# uC.net
KiCad netlist of a schematic drawn in Altium Designer
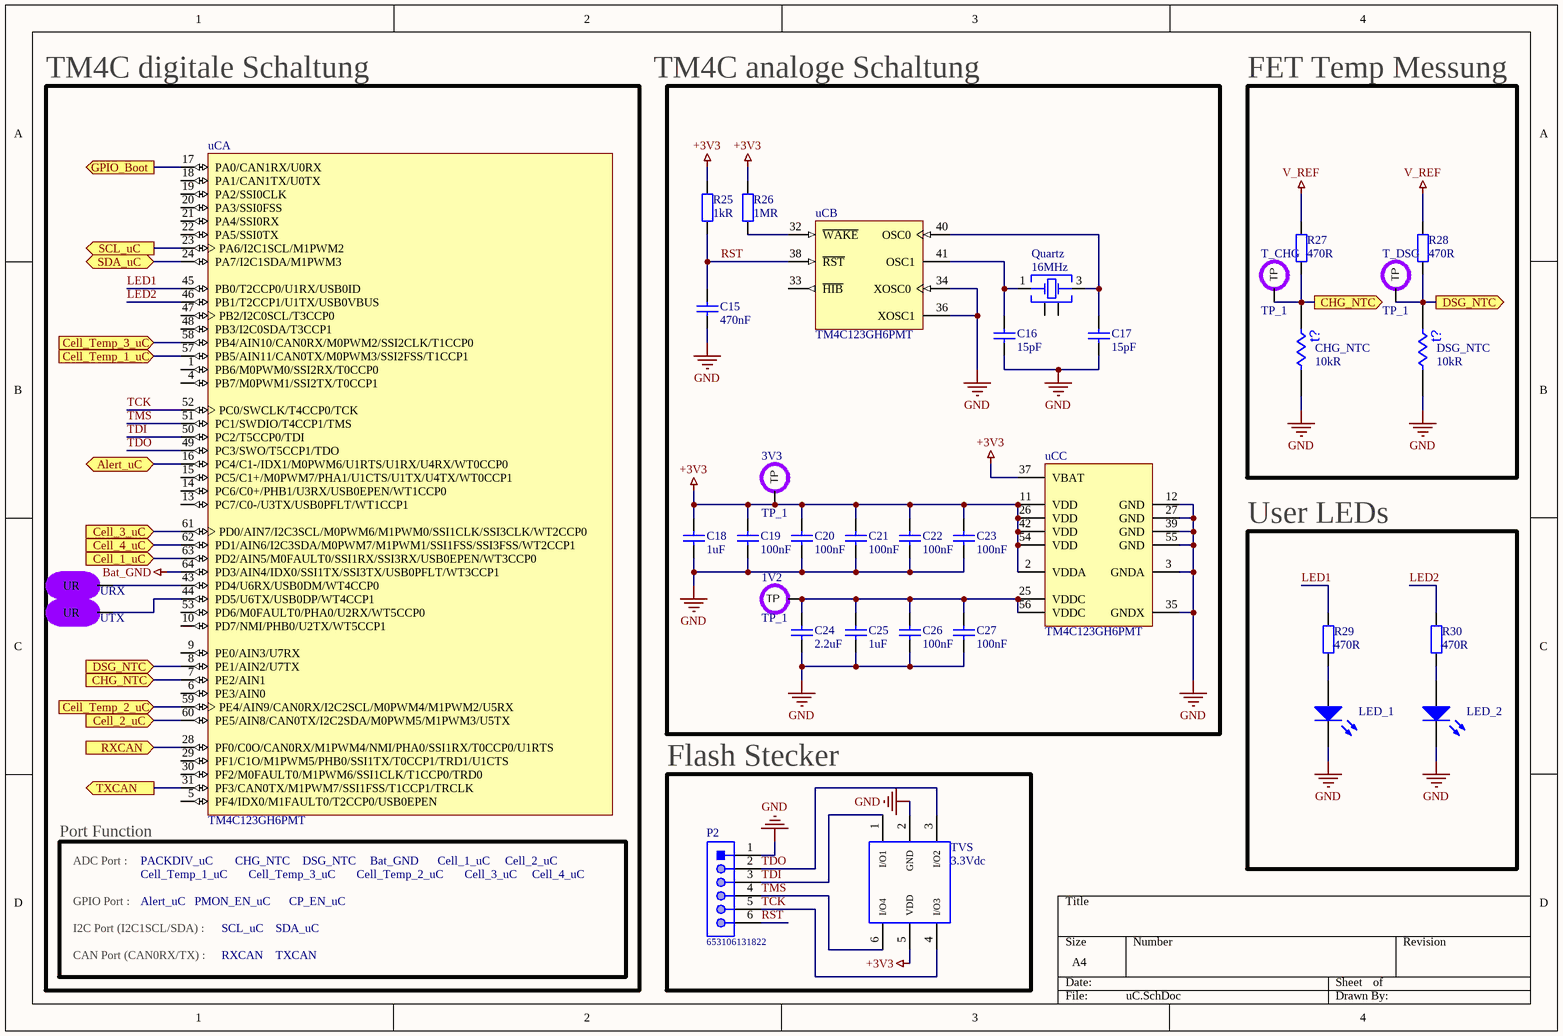
[diagram p0: uC.SchDoc]

(export (version "E")
  (design (tool "Eeschema 10.0.6"))
  (components
    (comp (ref "1V2")
      (value "TP_1")
      (footprint "Test point")
      (description "Power Supply for logical circuit")
      (libsource (lib "Schlib1") (part "Test point"))
    )
    (comp (ref "3V3")
      (value "TP_1")
      (footprint "Test point")
      (description "Power Supply for uC")
      (libsource (lib "Schlib1") (part "Test point"))
    )
    (comp (ref "C15")
      (value "470nF")
      (footprint "1608[0603]")
      (description "Capacitor")
      (fields (field (name "PUBLISHER") "Altium Limited"))
      (libsource (lib "Miscellaneous Devices") (part "Cap"))
    )
    (comp (ref "C16")
      (value "15pF")
      (footprint "1608[0603]")
      (description "Capacitor")
      (fields (field (name "PUBLISHER") "Altium Limited"))
      (libsource (lib "Miscellaneous Devices") (part "Cap"))
    )
    (comp (ref "C17")
      (value "15pF")
      (footprint "1608[0603]")
      (description "Capacitor")
      (fields (field (name "PUBLISHER") "Altium Limited"))
      (libsource (lib "Miscellaneous Devices") (part "Cap"))
    )
    (comp (ref "C18")
      (value "1uF")
      (footprint "1608[0603]")
      (description "Capacitor")
      (fields (field (name "PUBLISHER") "Altium Limited"))
      (libsource (lib "Miscellaneous Devices") (part "Cap"))
    )
    (comp (ref "C19")
      (value "100nF")
      (footprint "1608[0603]")
      (description "Capacitor")
      (fields (field (name "PUBLISHER") "Altium Limited"))
      (libsource (lib "Miscellaneous Devices") (part "Cap"))
    )
    (comp (ref "C20")
      (value "100nF")
      (footprint "1608[0603]")
      (description "Capacitor")
      (fields (field (name "PUBLISHER") "Altium Limited"))
      (libsource (lib "Miscellaneous Devices") (part "Cap"))
    )
    (comp (ref "C21")
      (value "100nF")
      (footprint "1608[0603]")
      (description "Capacitor")
      (fields (field (name "PUBLISHER") "Altium Limited"))
      (libsource (lib "Miscellaneous Devices") (part "Cap"))
    )
    (comp (ref "C22")
      (value "100nF")
      (footprint "1608[0603]")
      (description "Capacitor")
      (fields (field (name "PUBLISHER") "Altium Limited"))
      (libsource (lib "Miscellaneous Devices") (part "Cap"))
    )
    (comp (ref "C23")
      (value "100nF")
      (footprint "1608[0603]")
      (description "Capacitor")
      (fields (field (name "PUBLISHER") "Altium Limited"))
      (libsource (lib "Miscellaneous Devices") (part "Cap"))
    )
    (comp (ref "C24")
      (value "2.2uF")
      (footprint "1608[0603]")
      (description "Capacitor")
      (fields (field (name "PUBLISHER") "Altium Limited"))
      (libsource (lib "Miscellaneous Devices") (part "Cap"))
    )
    (comp (ref "C25")
      (value "1uF")
      (footprint "1608[0603]")
      (description "Capacitor")
      (fields (field (name "PUBLISHER") "Altium Limited"))
      (libsource (lib "Miscellaneous Devices") (part "Cap"))
    )
    (comp (ref "C26")
      (value "100nF")
      (footprint "1608[0603]")
      (description "Capacitor")
      (fields (field (name "PUBLISHER") "Altium Limited"))
      (libsource (lib "Miscellaneous Devices") (part "Cap"))
    )
    (comp (ref "C27")
      (value "100nF")
      (footprint "1608[0603]")
      (description "Capacitor")
      (fields (field (name "PUBLISHER") "Altium Limited"))
      (libsource (lib "Miscellaneous Devices") (part "Cap"))
    )
    (comp (ref "CHG_NTC")
      (value "10kR")
      (footprint "J1-0603")
      (description "Thermistor")
      (fields (field (name "PUBLISHER") "Altium Limited"))
      (libsource (lib "Miscellaneous Devices") (part "Res Thermal"))
    )
    (comp (ref "DSG_NTC")
      (value "10kR")
      (footprint "J1-0603")
      (description "Thermistor")
      (fields (field (name "PUBLISHER") "Altium Limited"))
      (libsource (lib "Miscellaneous Devices") (part "Res Thermal"))
    )
    (comp (ref "LED_1")
      (value "~")
      (footprint "1608[0603]")
      (description "Typical INFRARED GaAs LED")
      (fields (field (name "PUBLISHER") "Altium Limited"))
      (libsource (lib "Miscellaneous Devices") (part "LED0"))
    )
    (comp (ref "LED_2")
      (value "~")
      (footprint "1608[0603]")
      (description "Typical INFRARED GaAs LED")
      (fields (field (name "PUBLISHER") "Altium Limited"))
      (libsource (lib "Miscellaneous Devices") (part "LED0"))
    )
    (comp (ref "P2")
      (value "653106131822")
      (footprint "653106131822")
      (description "Male Shrouded Header WR-WTB, SMT, Right Angled, pitch 1.25 mm, 1 x 6 position")
      (fields (field (name "MANUFACTURER") "Wurth Elektronik") (field (name "PUBLISHER") "WurthElektronik"))
      (libsource (lib "Altium Content Vault") (part "WE-CN-1P-M-R6"))
    )
    (comp (ref "Quartz")
      (value "16MHz")
      (footprint "WE-XTAL_CFPX-180")
      (description "WE-XTAL Quartz Crystal, SMT, CFPX-180, 16MHz, +/-10ppm")
      (fields
        (field (name "MANUFACTURER PART NUMBER") "830108207109")
        (field (name "MANUFACTURER") "Wurth Elektronik")
      )
      (libsource (lib "Quartz Altium_WE-XTAL+(rev20c)") (part "830108207109"))
    )
    (comp (ref "R25")
      (value "1kR")
      (footprint "J1-0603")
      (description "Resistor")
      (fields (field (name "PUBLISHER") "Altium Limited"))
      (libsource (lib "") (part "Res2_1"))
    )
    (comp (ref "R26")
      (value "1MR")
      (footprint "J1-0603")
      (description "Resistor")
      (fields (field (name "PUBLISHER") "Altium Limited"))
      (libsource (lib "") (part "Res2_1"))
    )
    (comp (ref "R27")
      (value "470R")
      (footprint "J1-0603")
      (description "Resistor")
      (fields (field (name "PUBLISHER") "Altium Limited"))
      (libsource (lib "Miscellaneous Devices") (part "Res2"))
    )
    (comp (ref "R28")
      (value "470R")
      (footprint "J1-0603")
      (description "Resistor")
      (fields (field (name "PUBLISHER") "Altium Limited"))
      (libsource (lib "Miscellaneous Devices") (part "Res2"))
    )
    (comp (ref "R29")
      (value "470R")
      (footprint "J1-0603")
      (description "Resistor")
      (fields (field (name "PUBLISHER") "Altium Limited"))
      (libsource (lib "") (part "Res2_1"))
    )
    (comp (ref "R30")
      (value "470R")
      (footprint "J1-0603")
      (description "Resistor")
      (fields (field (name "PUBLISHER") "Altium Limited"))
      (libsource (lib "") (part "Res2_1"))
    )
    (comp (ref "TVS")
      (value "3.3Vdc")
      (footprint "WE-TVS_SOT23-6L")
      (description "WE-TVS TVS Diode - High Speed Series, SOT23-6L, 4+1Channel, 3.3Vdc")
      (fields
        (field (name "MANUFACTURER PART NUMBER") "824013")
        (field (name "MANUFACTURER") "Wurth Elektronik")
      )
      (libsource (lib "Altium_WE-TVS (rev20a)") (part "824013"))
    )
    (comp (ref "T_CHG")
      (value "TP_1")
      (footprint "Test point")
      (libsource (lib "Schlib1") (part "Test point"))
    )
    (comp (ref "T_DSG")
      (value "TP_1")
      (footprint "Test point")
      (libsource (lib "Schlib1") (part "Test point"))
    )
    (comp (ref "uC")
      (value "TM4C123GH6PMT")
      (footprint "PM0064A_L")
      (fields (field (name "MANUFACTURER") "Texas Instruments"))
      (libsource (lib "Altium Content Vault") (part "TI-TM4C123GH6PM-LQFP-64"))
    )
    (comp (ref "URX") (value "UR") (footprint "UR Pad") (libsource (lib "Schlib1") (part "UR Pad")))
    (comp (ref "UTX") (value "UR") (footprint "UR Pad") (libsource (lib "Schlib1") (part "UR Pad")))
  )
  (nets
    (net (code "1") (name "+3V3") (class "Default")
      (node (ref "3V3") (pin "1") (pinfunction "TP_1") (pintype "passive"))
      (node (ref "C18") (pin "1") (pinfunction "1_1") (pintype "passive"))
      (node (ref "C19") (pin "1") (pinfunction "1_1") (pintype "passive"))
      (node (ref "C20") (pin "1") (pinfunction "1_1") (pintype "passive"))
      (node (ref "C21") (pin "1") (pinfunction "1_1") (pintype "passive"))
      (node (ref "C22") (pin "1") (pinfunction "1_1") (pintype "passive"))
      (node (ref "C23") (pin "1") (pinfunction "1_1") (pintype "passive"))
      (node (ref "R25") (pin "1") (pinfunction "1_1") (pintype "passive"))
      (node (ref "R26") (pin "1") (pinfunction "1_1") (pintype "passive"))
      (node (ref "TVS") (pin "5") (pinfunction "VDD_5") (pintype "passive"))
      (node (ref "uC") (pin "11") (pinfunction "VDD_11") (pintype "power_in"))
      (node (ref "uC") (pin "2") (pinfunction "VDDA_2") (pintype "power_in"))
      (node (ref "uC") (pin "26") (pinfunction "VDD_26") (pintype "power_in"))
      (node (ref "uC") (pin "37") (pinfunction "VBAT_37") (pintype "power_in"))
      (node (ref "uC") (pin "42") (pinfunction "VDD_42") (pintype "power_in"))
      (node (ref "uC") (pin "54") (pinfunction "VDD_54") (pintype "power_in"))
    )
    (net (code "2") (name "/Alert_uC") (class "Default")
      (node (ref "uC") (pin "16") (pinfunction "PC4/C1-/IDX1/M0PWM6/U1RTS/U1RX/U4RX/WT0CCP0_16") (pintype "bidirectional"))
    )
    (net (code "3") (name "/CHG_NTC") (class "Default")
      (node (ref "CHG_NTC") (pin "1") (pinfunction "1_1") (pintype "passive"))
      (node (ref "R27") (pin "2") (pinfunction "2_2") (pintype "passive"))
      (node (ref "T_CHG") (pin "1") (pinfunction "TP_1") (pintype "passive"))
      (node (ref "uC") (pin "7") (pinfunction "PE2/AIN1_7") (pintype "bidirectional"))
    )
    (net (code "4") (name "/Cell_1_uC") (class "Default")
      (node (ref "uC") (pin "63") (pinfunction "PD2/AIN5/M0FAULT0/SSI1RX/SSI3RX/USB0EPEN/WT3CCP0_63") (pintype "bidirectional"))
    )
    (net (code "5") (name "/Cell_2_uC") (class "Default")
      (node (ref "uC") (pin "60") (pinfunction "PE5/AIN8/CAN0TX/I2C2SDA/M0PWM5/M1PWM3/U5TX_60") (pintype "bidirectional"))
    )
    (net (code "6") (name "/Cell_3_uC") (class "Default")
      (node (ref "uC") (pin "61") (pinfunction "PD0/AIN7/I2C3SCL/M0PWM6/M1PWM0/SSI1CLK/SSI3CLK/WT2CCP0_61") (pintype "bidirectional"))
    )
    (net (code "7") (name "/Cell_4_uC") (class "Default")
      (node (ref "uC") (pin "62") (pinfunction "PD1/AIN6/I2C3SDA/M0PWM7/M1PWM1/SSI1FSS/SSI3FSS/WT2CCP1_62") (pintype "bidirectional"))
    )
    (net (code "8") (name "/Cell_Temp_1_uC") (class "Default")
      (node (ref "uC") (pin "57") (pinfunction "PB5/AIN11/CAN0TX/M0PWM3/SSI2FSS/T1CCP1_57") (pintype "bidirectional"))
    )
    (net (code "9") (name "/Cell_Temp_2_uC") (class "Default")
      (node (ref "uC") (pin "59") (pinfunction "PE4/AIN9/CAN0RX/I2C2SCL/M0PWM4/M1PWM2/U5RX_59") (pintype "bidirectional"))
    )
    (net (code "10") (name "/Cell_Temp_3_uC") (class "Default")
      (node (ref "uC") (pin "58") (pinfunction "PB4/AIN10/CAN0RX/M0PWM2/SSI2CLK/T1CCP0_58") (pintype "bidirectional"))
    )
    (net (code "11") (name "/DSG_NTC") (class "Default")
      (node (ref "DSG_NTC") (pin "1") (pinfunction "1_1") (pintype "passive"))
      (node (ref "R28") (pin "2") (pinfunction "2_2") (pintype "passive"))
      (node (ref "T_DSG") (pin "1") (pinfunction "TP_1") (pintype "passive"))
      (node (ref "uC") (pin "8") (pinfunction "PE1/AIN2/U7TX_8") (pintype "bidirectional"))
    )
    (net (code "12") (name "/GPIO_Boot") (class "Default")
      (node (ref "uC") (pin "17") (pinfunction "PA0/CAN1RX/U0RX_17") (pintype "bidirectional"))
    )
    (net (code "13") (name "/LED1") (class "Default")
      (node (ref "R29") (pin "1") (pinfunction "1_1") (pintype "passive"))
      (node (ref "uC") (pin "45") (pinfunction "PB0/T2CCP0/U1RX/USB0ID_45") (pintype "bidirectional"))
    )
    (net (code "14") (name "/LED2") (class "Default")
      (node (ref "R30") (pin "1") (pinfunction "1_1") (pintype "passive"))
      (node (ref "uC") (pin "46") (pinfunction "PB1/T2CCP1/U1TX/USB0VBUS_46") (pintype "bidirectional"))
    )
    (net (code "15") (name "/RST") (class "Default")
      (node (ref "C15") (pin "1") (pinfunction "1_1") (pintype "passive"))
      (node (ref "P2") (pin "6") (pinfunction "6_6") (pintype "passive"))
      (node (ref "R25") (pin "2") (pinfunction "2_2") (pintype "passive"))
      (node (ref "uC") (pin "38") (pinfunction "~{RST}_38") (pintype "input"))
    )
    (net (code "16") (name "/RXCAN") (class "Default")
      (node (ref "uC") (pin "28") (pinfunction "PF0/C0O/CAN0RX/M1PWM4/NMI/PHA0/SSI1RX/T0CCP0/U1RTS_28") (pintype "bidirectional"))
    )
    (net (code "17") (name "/SCL_uC") (class "Default")
      (node (ref "uC") (pin "23") (pinfunction "PA6/I2C1SCL/M1PWM2_23") (pintype "bidirectional"))
    )
    (net (code "18") (name "/SDA_uC") (class "Default")
      (node (ref "uC") (pin "24") (pinfunction "PA7/I2C1SDA/M1PWM3_24") (pintype "bidirectional"))
    )
    (net (code "19") (name "/TCK") (class "Default")
      (node (ref "P2") (pin "5") (pinfunction "5_5") (pintype "passive"))
      (node (ref "TVS") (pin "4") (pinfunction "I/O3_4") (pintype "passive"))
      (node (ref "uC") (pin "52") (pinfunction "PC0/SWCLK/T4CCP0/TCK_52") (pintype "bidirectional"))
    )
    (net (code "20") (name "/TDI") (class "Default")
      (node (ref "P2") (pin "3") (pinfunction "3_3") (pintype "passive"))
      (node (ref "TVS") (pin "1") (pinfunction "I/O1_1") (pintype "passive"))
      (node (ref "uC") (pin "50") (pinfunction "PC2/T5CCP0/TDI_50") (pintype "bidirectional"))
    )
    (net (code "21") (name "/TDO") (class "Default")
      (node (ref "P2") (pin "2") (pinfunction "2_2") (pintype "passive"))
      (node (ref "TVS") (pin "3") (pinfunction "I/O2_3") (pintype "passive"))
      (node (ref "uC") (pin "49") (pinfunction "PC3/SWO/T5CCP1/TDO_49") (pintype "bidirectional"))
    )
    (net (code "22") (name "/TMS") (class "Default")
      (node (ref "P2") (pin "4") (pinfunction "4_4") (pintype "passive"))
      (node (ref "TVS") (pin "6") (pinfunction "I/O4_6") (pintype "passive"))
      (node (ref "uC") (pin "51") (pinfunction "PC1/SWDIO/T4CCP1/TMS_51") (pintype "bidirectional"))
    )
    (net (code "23") (name "/TXCAN") (class "Default")
      (node (ref "uC") (pin "31") (pinfunction "PF3/CAN0TX/M1PWM7/SSI1FSS/T1CCP1/TRCLK_31") (pintype "bidirectional"))
    )
    (net (code "24") (name "Bat_GND") (class "Default")
      (node (ref "uC") (pin "64") (pinfunction "PD3/AIN4/IDX0/SSI1TX/SSI3TX/USB0PFLT/WT3CCP1_64") (pintype "bidirectional"))
    )
    (net (code "25") (name "GND") (class "Default")
      (node (ref "C15") (pin "2") (pinfunction "2_2") (pintype "passive"))
      (node (ref "C16") (pin "2") (pinfunction "2_2") (pintype "passive"))
      (node (ref "C17") (pin "2") (pinfunction "2_2") (pintype "passive"))
      (node (ref "C18") (pin "2") (pinfunction "2_2") (pintype "passive"))
      (node (ref "C19") (pin "2") (pinfunction "2_2") (pintype "passive"))
      (node (ref "C20") (pin "2") (pinfunction "2_2") (pintype "passive"))
      (node (ref "C21") (pin "2") (pinfunction "2_2") (pintype "passive"))
      (node (ref "C22") (pin "2") (pinfunction "2_2") (pintype "passive"))
      (node (ref "C23") (pin "2") (pinfunction "2_2") (pintype "passive"))
      (node (ref "C24") (pin "2") (pinfunction "2_2") (pintype "passive"))
      (node (ref "C25") (pin "2") (pinfunction "2_2") (pintype "passive"))
      (node (ref "C26") (pin "2") (pinfunction "2_2") (pintype "passive"))
      (node (ref "C27") (pin "2") (pinfunction "2_2") (pintype "passive"))
      (node (ref "CHG_NTC") (pin "2") (pinfunction "2_2") (pintype "passive"))
      (node (ref "DSG_NTC") (pin "2") (pinfunction "2_2") (pintype "passive"))
      (node (ref "LED_1") (pin "2") (pinfunction "K_2") (pintype "passive"))
      (node (ref "LED_2") (pin "2") (pinfunction "K_2") (pintype "passive"))
      (node (ref "P2") (pin "1") (pinfunction "1_1") (pintype "passive"))
      (node (ref "TVS") (pin "2") (pinfunction "GND_2") (pintype "passive"))
      (node (ref "uC") (pin "12") (pinfunction "GND_12") (pintype "power_in"))
      (node (ref "uC") (pin "27") (pinfunction "GND_27") (pintype "power_in"))
      (node (ref "uC") (pin "3") (pinfunction "GNDA_3") (pintype "power_in"))
      (node (ref "uC") (pin "34") (pinfunction "XOSC0_34") (pintype "input"))
      (node (ref "uC") (pin "35") (pinfunction "GNDX_35") (pintype "power_in"))
      (node (ref "uC") (pin "36") (pinfunction "XOSC1_36") (pintype "passive"))
      (node (ref "uC") (pin "39") (pinfunction "GND_39") (pintype "power_in"))
      (node (ref "uC") (pin "55") (pinfunction "GND_55") (pintype "power_in"))
    )
    (net (code "26") (name "Net-(1V2-TP)") (class "Default")
      (node (ref "1V2") (pin "1") (pinfunction "TP_1") (pintype "passive"))
      (node (ref "C24") (pin "1") (pinfunction "1_1") (pintype "passive"))
      (node (ref "C25") (pin "1") (pinfunction "1_1") (pintype "passive"))
      (node (ref "C26") (pin "1") (pinfunction "1_1") (pintype "passive"))
      (node (ref "C27") (pin "1") (pinfunction "1_1") (pintype "passive"))
      (node (ref "uC") (pin "25") (pinfunction "VDDC_25") (pintype "power_in"))
      (node (ref "uC") (pin "56") (pinfunction "VDDC_56") (pintype "power_in"))
    )
    (net (code "27") (name "Net-(LED_1-A)") (class "Default")
      (node (ref "LED_1") (pin "1") (pinfunction "A_1") (pintype "passive"))
      (node (ref "R29") (pin "2") (pinfunction "2_2") (pintype "passive"))
    )
    (net (code "28") (name "Net-(LED_2-A)") (class "Default")
      (node (ref "LED_2") (pin "1") (pinfunction "A_1") (pintype "passive"))
      (node (ref "R30") (pin "2") (pinfunction "2_2") (pintype "passive"))
    )
    (net (code "29") (name "Net-(URX-UR)") (class "Default")
      (node (ref "URX") (pin "1") (pinfunction "UR_1") (pintype "passive"))
      (node (ref "uC") (pin "43") (pinfunction "PD4/U6RX/USB0DM/WT4CCP0_43") (pintype "bidirectional"))
    )
    (net (code "30") (name "Net-(UTX-UR)") (class "Default")
      (node (ref "UTX") (pin "1") (pinfunction "UR_1") (pintype "passive"))
      (node (ref "uC") (pin "44") (pinfunction "PD5/U6TX/USB0DP/WT4CCP1_44") (pintype "bidirectional"))
    )
    (net (code "31") (name "Net-(uCB-OSC0)") (class "Default")
      (node (ref "C17") (pin "1") (pinfunction "1_1") (pintype "passive"))
      (node (ref "Quartz") (pin "3") (pinfunction "Crystal_3") (pintype "passive"))
      (node (ref "uC") (pin "40") (pinfunction "OSC0_40") (pintype "input"))
    )
    (net (code "32") (name "Net-(uCB-OSC1)") (class "Default")
      (node (ref "C16") (pin "1") (pinfunction "1_1") (pintype "passive"))
      (node (ref "Quartz") (pin "1") (pinfunction "Crystal_1") (pintype "passive"))
      (node (ref "uC") (pin "41") (pinfunction "OSC1_41") (pintype "passive"))
    )
    (net (code "33") (name "Net-(uCB-~{WAKE})") (class "Default")
      (node (ref "R26") (pin "2") (pinfunction "2_2") (pintype "passive"))
      (node (ref "uC") (pin "32") (pinfunction "~{WAKE}_32") (pintype "input"))
    )
    (net (code "34") (name "V_REF") (class "Default")
      (node (ref "R27") (pin "1") (pinfunction "1_1") (pintype "passive"))
      (node (ref "R28") (pin "1") (pinfunction "1_1") (pintype "passive"))
    )
    (net (code "35") (name "unconnected-(Quartz-GND-Pad2)") (class "Default")
      (node (ref "Quartz") (pin "2") (pinfunction "GND_2") (pintype "passive"))
    )
    (net (code "36") (name "unconnected-(Quartz-GND-Pad4)") (class "Default")
      (node (ref "Quartz") (pin "4") (pinfunction "GND_4") (pintype "passive"))
    )
    (net (code "37") (name "unconnected-(uCA-PA1{slash}CAN1TX{slash}U0TX-Pad18)") (class "Default")
      (node (ref "uC") (pin "18") (pinfunction "PA1/CAN1TX/U0TX_18") (pintype "bidirectional"))
    )
    (net (code "38") (name "unconnected-(uCA-PA2{slash}SSI0CLK-Pad19)") (class "Default")
      (node (ref "uC") (pin "19") (pinfunction "PA2/SSI0CLK_19") (pintype "bidirectional"))
    )
    (net (code "39") (name "unconnected-(uCA-PA3{slash}SSI0FSS-Pad20)") (class "Default")
      (node (ref "uC") (pin "20") (pinfunction "PA3/SSI0FSS_20") (pintype "bidirectional"))
    )
    (net (code "40") (name "unconnected-(uCA-PA4{slash}SSI0RX-Pad21)") (class "Default")
      (node (ref "uC") (pin "21") (pinfunction "PA4/SSI0RX_21") (pintype "bidirectional"))
    )
    (net (code "41") (name "unconnected-(uCA-PA5{slash}SSI0TX-Pad22)") (class "Default")
      (node (ref "uC") (pin "22") (pinfunction "PA5/SSI0TX_22") (pintype "bidirectional"))
    )
    (net (code "42") (name "unconnected-(uCA-PB2{slash}I2C0SCL{slash}T3CCP0-Pad47)") (class "Default")
      (node (ref "uC") (pin "47") (pinfunction "PB2/I2C0SCL/T3CCP0_47") (pintype "bidirectional"))
    )
    (net (code "43") (name "unconnected-(uCA-PB3{slash}I2C0SDA{slash}T3CCP1-Pad48)") (class "Default")
      (node (ref "uC") (pin "48") (pinfunction "PB3/I2C0SDA/T3CCP1_48") (pintype "bidirectional"))
    )
    (net (code "44") (name "unconnected-(uCA-PB6{slash}M0PWM0{slash}SSI2RX{slash}T0CCP0-Pad1)") (class "Default")
      (node (ref "uC") (pin "1") (pinfunction "PB6/M0PWM0/SSI2RX/T0CCP0_1") (pintype "bidirectional"))
    )
    (net (code "45") (name "unconnected-(uCA-PB7{slash}M0PWM1{slash}SSI2TX{slash}T0CCP1-Pad4)") (class "Default")
      (node (ref "uC") (pin "4") (pinfunction "PB7/M0PWM1/SSI2TX/T0CCP1_4") (pintype "bidirectional"))
    )
    (net (code "46") (name "unconnected-(uCA-PC5{slash}C1+{slash}M0PWM7{slash}PHA1{slash}U1CTS{slash}U1TX{slash}U4TX{slash}WT0CCP1-Pad15)") (class "Default")
      (node (ref "uC") (pin "15") (pinfunction "PC5/C1+/M0PWM7/PHA1/U1CTS/U1TX/U4TX/WT0CCP1_15") (pintype "bidirectional"))
    )
    (net (code "47") (name "unconnected-(uCA-PC6{slash}C0+{slash}PHB1{slash}U3RX{slash}USB0EPEN{slash}WT1CCP0-Pad14)") (class "Default")
      (node (ref "uC") (pin "14") (pinfunction "PC6/C0+/PHB1/U3RX/USB0EPEN/WT1CCP0_14") (pintype "bidirectional"))
    )
    (net (code "48") (name "unconnected-(uCA-PC7{slash}C0-{slash}U3TX{slash}USB0PFLT{slash}WT1CCP1-Pad13)") (class "Default")
      (node (ref "uC") (pin "13") (pinfunction "PC7/C0-/U3TX/USB0PFLT/WT1CCP1_13") (pintype "bidirectional"))
    )
    (net (code "49") (name "unconnected-(uCA-PD6{slash}M0FAULT0{slash}PHA0{slash}U2RX{slash}WT5CCP0-Pad53)") (class "Default")
      (node (ref "uC") (pin "53") (pinfunction "PD6/M0FAULT0/PHA0/U2RX/WT5CCP0_53") (pintype "bidirectional"))
    )
    (net (code "50") (name "unconnected-(uCA-PD7{slash}NMI{slash}PHB0{slash}U2TX{slash}WT5CCP1-Pad10)") (class "Default")
      (node (ref "uC") (pin "10") (pinfunction "PD7/NMI/PHB0/U2TX/WT5CCP1_10") (pintype "bidirectional"))
    )
    (net (code "51") (name "unconnected-(uCA-PE0{slash}AIN3{slash}U7RX-Pad9)") (class "Default")
      (node (ref "uC") (pin "9") (pinfunction "PE0/AIN3/U7RX_9") (pintype "bidirectional"))
    )
    (net (code "52") (name "unconnected-(uCA-PE3{slash}AIN0-Pad6)") (class "Default")
      (node (ref "uC") (pin "6") (pinfunction "PE3/AIN0_6") (pintype "bidirectional"))
    )
    (net (code "53") (name "unconnected-(uCA-PF1{slash}C1O{slash}M1PWM5{slash}PHB0{slash}SSI1TX{slash}T0CCP1{slash}TRD1{slash}U1CTS-Pad29)") (class "Default")
      (node (ref "uC") (pin "29") (pinfunction "PF1/C1O/M1PWM5/PHB0/SSI1TX/T0CCP1/TRD1/U1CTS_29") (pintype "bidirectional"))
    )
    (net (code "54") (name "unconnected-(uCA-PF2{slash}M0FAULT0{slash}M1PWM6{slash}SSI1CLK{slash}T1CCP0{slash}TRD0-Pad30)") (class "Default")
      (node (ref "uC") (pin "30") (pinfunction "PF2/M0FAULT0/M1PWM6/SSI1CLK/T1CCP0/TRD0_30") (pintype "bidirectional"))
    )
    (net (code "55") (name "unconnected-(uCA-PF4{slash}IDX0{slash}M1FAULT0{slash}T2CCP0{slash}USB0EPEN-Pad5)") (class "Default")
      (node (ref "uC") (pin "5") (pinfunction "PF4/IDX0/M1FAULT0/T2CCP0/USB0EPEN_5") (pintype "bidirectional"))
    )
    (net (code "56") (name "unconnected-(uCB-~{HIB}-Pad33)") (class "Default")
      (node (ref "uC") (pin "33") (pinfunction "~{HIB}_33") (pintype "output"))
    )
  )
)
